# NTP_GPS_V1_0.net
KiCad netlist of a schematic drawn in EAGLE
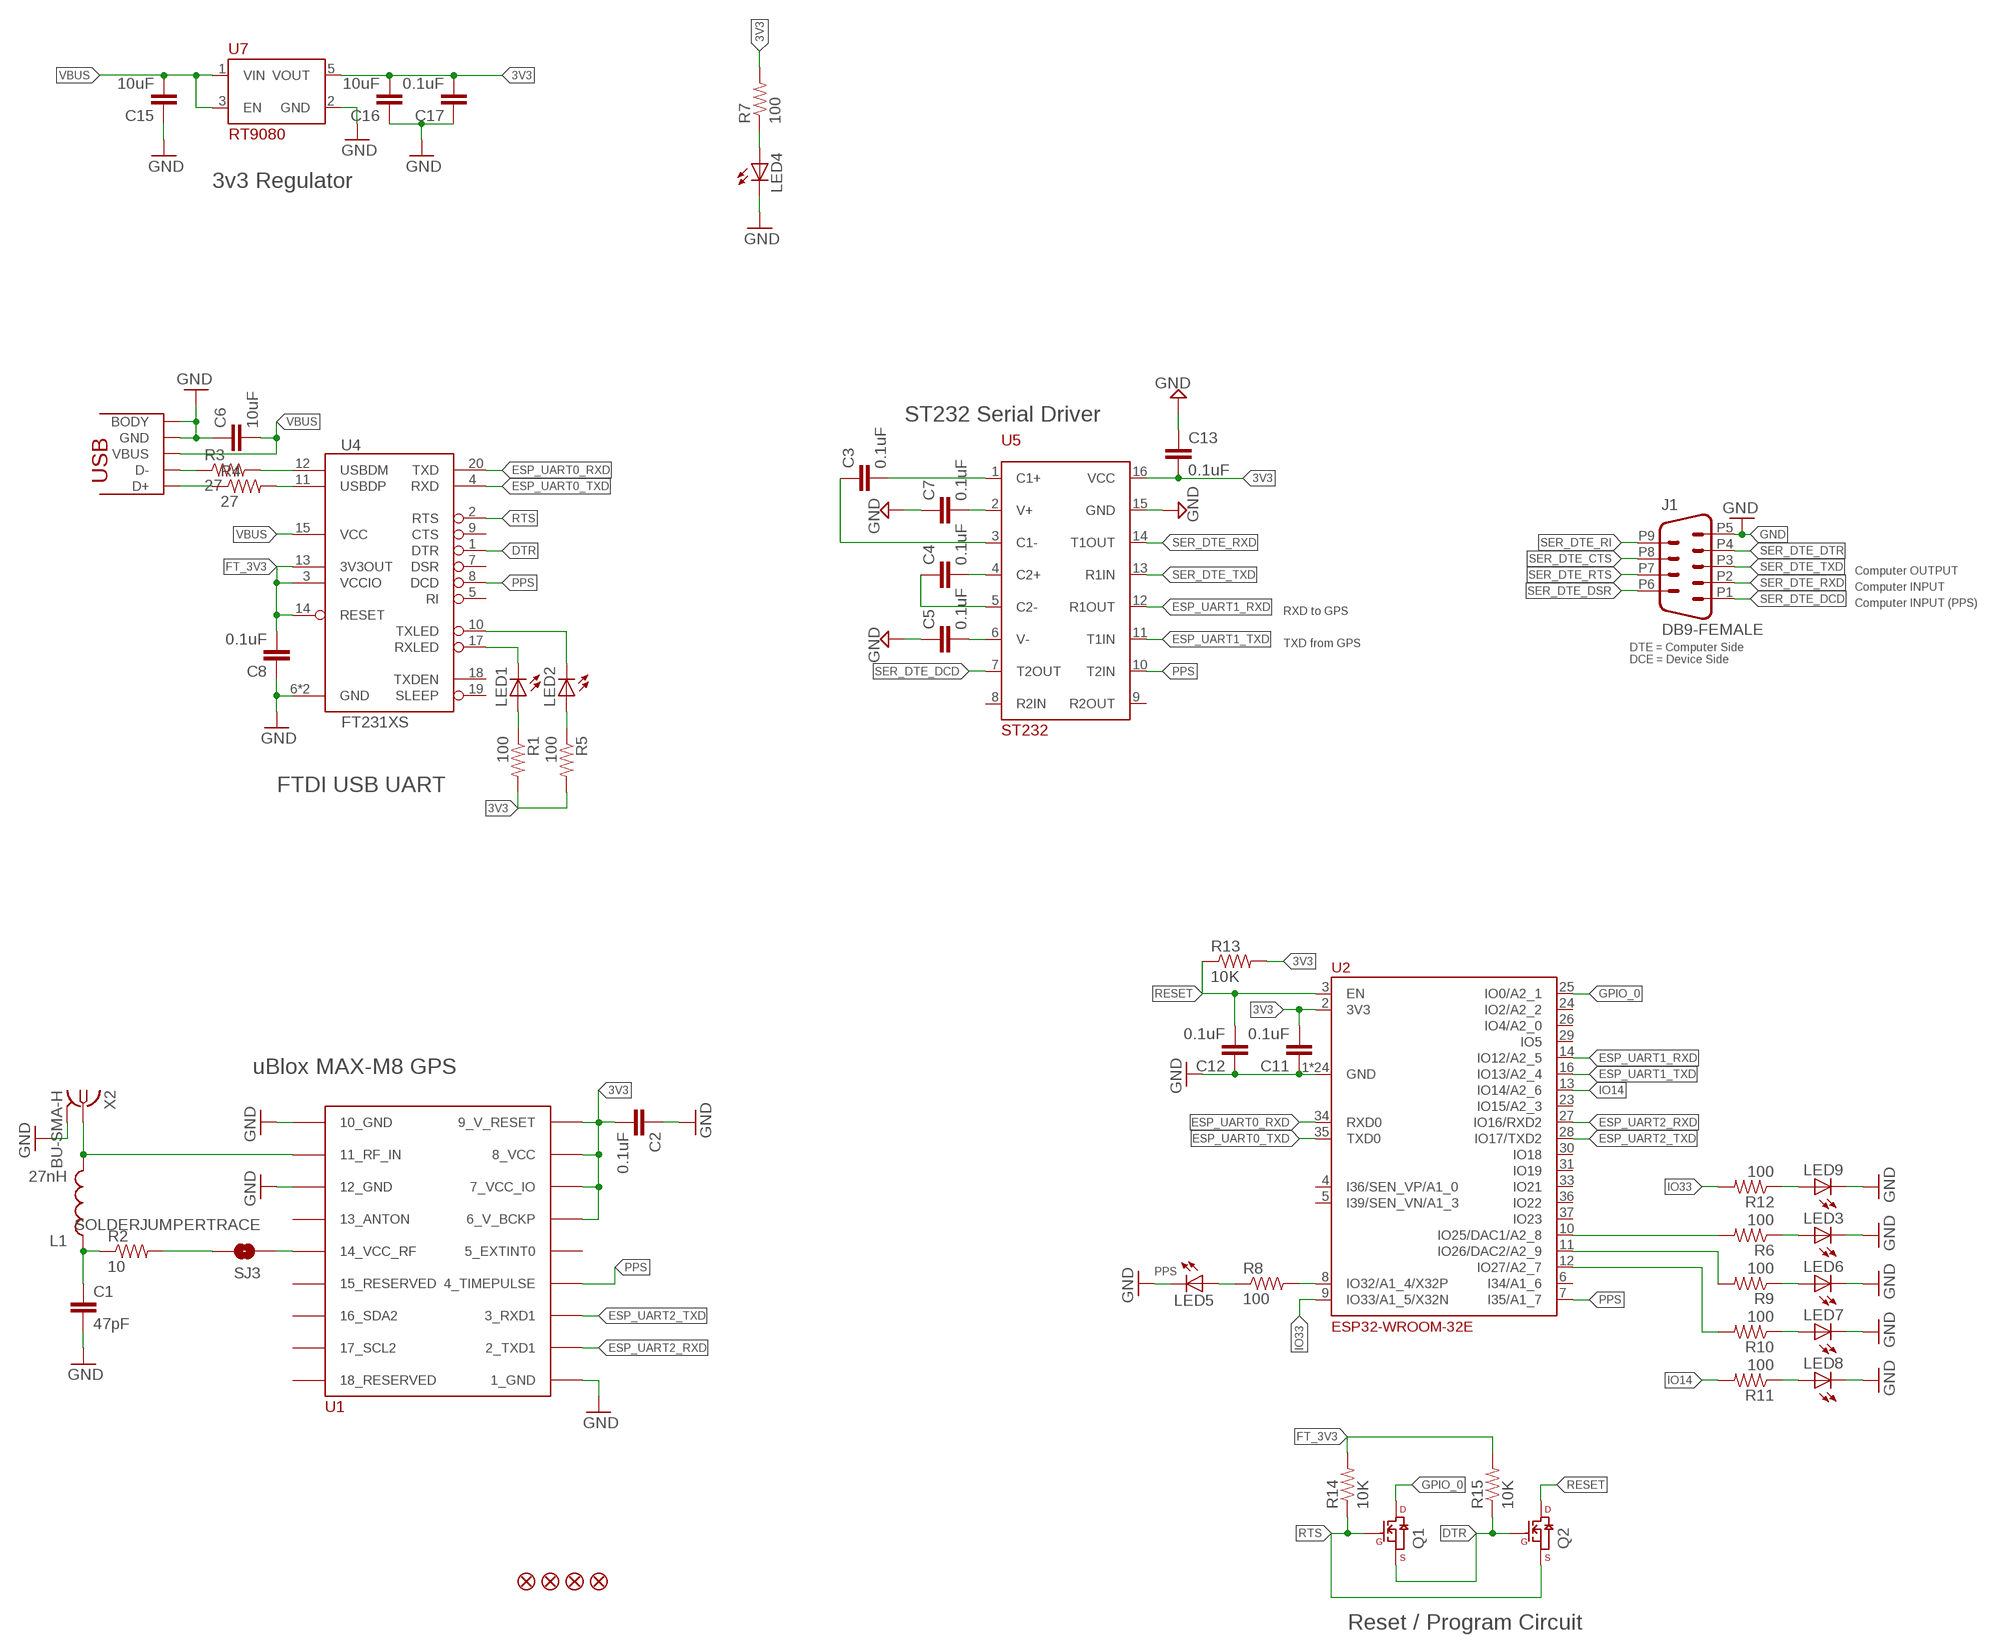
[diagram p0: schematic, sheet 1]

(export (version "E")
  (design (tool "Eeschema 10.0.6"))
  (components
    (comp (ref "C1")
      (value "47pF")
      (footprint "eagle-import:0603-CAP")
      (libsource (lib "eagle-import") (part "CAP0603-CAP"))
    )
    (comp (ref "C2")
      (value "0.1uF")
      (footprint "eagle-import:0603-CAP")
      (libsource (lib "eagle-import") (part "CAP0603-CAP"))
    )
    (comp (ref "C3")
      (value "0.1uF")
      (footprint "eagle-import:0603-CAP")
      (libsource (lib "eagle-import") (part "CAP0603-CAP"))
    )
    (comp (ref "C4")
      (value "0.1uF")
      (footprint "eagle-import:0603-CAP")
      (libsource (lib "eagle-import") (part "CAP0603-CAP"))
    )
    (comp (ref "C5")
      (value "0.1uF")
      (footprint "eagle-import:0603-CAP")
      (libsource (lib "eagle-import") (part "CAP0603-CAP"))
    )
    (comp (ref "C6")
      (value "10uF")
      (footprint "eagle-import:1206")
      (libsource (lib "eagle-import") (part "CAP1206"))
    )
    (comp (ref "C7")
      (value "0.1uF")
      (footprint "eagle-import:0603-CAP")
      (libsource (lib "eagle-import") (part "CAP0603-CAP"))
    )
    (comp (ref "C8")
      (value "0.1uF")
      (footprint "eagle-import:0603-CAP")
      (libsource (lib "eagle-import") (part "CAP0603-CAP"))
    )
    (comp (ref "C11")
      (value "0.1uF")
      (footprint "eagle-import:0603-CAP")
      (libsource (lib "eagle-import") (part "CAP0603-CAP"))
    )
    (comp (ref "C12")
      (value "0.1uF")
      (footprint "eagle-import:0603-CAP")
      (libsource (lib "eagle-import") (part "CAP0603-CAP"))
    )
    (comp (ref "C13")
      (value "0.1uF")
      (footprint "eagle-import:0603-CAP")
      (libsource (lib "eagle-import") (part "CAP0603-CAP"))
    )
    (comp (ref "C15")
      (value "10uF")
      (footprint "eagle-import:1206")
      (libsource (lib "eagle-import") (part "CAP1206"))
    )
    (comp (ref "C16")
      (value "10uF")
      (footprint "eagle-import:1206")
      (libsource (lib "eagle-import") (part "CAP1206"))
    )
    (comp (ref "C17")
      (value "0.1uF")
      (footprint "eagle-import:0603-CAP")
      (libsource (lib "eagle-import") (part "CAP0603-CAP"))
    )
    (comp (ref "FID1")
      (value "FIDUCIAL")
      (footprint "eagle-import:FIDUCIAL")
      (libsource (lib "eagle-import") (part "FIDUCIAL"))
    )
    (comp (ref "FID2")
      (value "FIDUCIAL")
      (footprint "eagle-import:FIDUCIAL")
      (libsource (lib "eagle-import") (part "FIDUCIAL"))
    )
    (comp (ref "FID3")
      (value "FIDUCIAL")
      (footprint "eagle-import:FIDUCIAL")
      (libsource (lib "eagle-import") (part "FIDUCIAL"))
    )
    (comp (ref "FID4")
      (value "FIDUCIAL")
      (footprint "eagle-import:FIDUCIAL")
      (libsource (lib "eagle-import") (part "FIDUCIAL"))
    )
    (comp (ref "J1")
      (value "DB9-FEMALE")
      (footprint "eagle-import:AMP_DELTAD_D09S13B4GV00LF")
      (libsource (lib "eagle-import") (part "DB9-FEMALE"))
    )
    (comp (ref "L1")
      (value "27nH")
      (footprint "eagle-import:0603")
      (libsource (lib "eagle-import") (part "INDUCTOR0603"))
    )
    (comp (ref "LED1")
      (value "LED")
      (footprint "eagle-import:LED_QBL7XX80D-MP4A")
      (libsource (lib "eagle-import") (part "LED"))
    )
    (comp (ref "LED2")
      (value "LED")
      (footprint "eagle-import:LED_QBL7XX80D-MP4A")
      (libsource (lib "eagle-import") (part "LED"))
    )
    (comp (ref "LED3")
      (value "LED")
      (footprint "eagle-import:LED_QBL7XX80D-MP4A")
      (libsource (lib "eagle-import") (part "LED"))
    )
    (comp (ref "LED4")
      (value "LED")
      (footprint "eagle-import:LED_QBL7XX80D-MP4A")
      (libsource (lib "eagle-import") (part "LED"))
    )
    (comp (ref "LED5")
      (value "LED")
      (footprint "eagle-import:LED_QBL7XX80D-MP4A")
      (libsource (lib "eagle-import") (part "LED"))
    )
    (comp (ref "LED6")
      (value "LED")
      (footprint "eagle-import:LED_QBL7XX80D-MP4A")
      (libsource (lib "eagle-import") (part "LED"))
    )
    (comp (ref "LED7")
      (value "LED")
      (footprint "eagle-import:LED_QBL7XX80D-MP4A")
      (libsource (lib "eagle-import") (part "LED"))
    )
    (comp (ref "LED8")
      (value "LED")
      (footprint "eagle-import:LED_QBL7XX80D-MP4A")
      (libsource (lib "eagle-import") (part "LED"))
    )
    (comp (ref "LED9")
      (value "LED")
      (footprint "eagle-import:LED_QBL7XX80D-MP4A")
      (libsource (lib "eagle-import") (part "LED"))
    )
    (comp (ref "Q1")
      (value "MOSFET_N_CHANNELSI1308")
      (footprint "eagle-import:SC-70-3")
      (libsource (lib "eagle-import") (part "MOSFET_N_CHANNELSI1308"))
    )
    (comp (ref "Q2")
      (value "MOSFET_N_CHANNELSI1308")
      (footprint "eagle-import:SC-70-3")
      (libsource (lib "eagle-import") (part "MOSFET_N_CHANNELSI1308"))
    )
    (comp (ref "R1")
      (value "100")
      (footprint "eagle-import:0603-RES")
      (libsource (lib "eagle-import") (part "RESISTOR0603-RES"))
    )
    (comp (ref "R2")
      (value "10")
      (footprint "eagle-import:0603-RES")
      (libsource (lib "eagle-import") (part "RESISTOR0603-RES"))
    )
    (comp (ref "R3")
      (value "27")
      (footprint "eagle-import:0603-RES")
      (libsource (lib "eagle-import") (part "RESISTOR0603-RES"))
    )
    (comp (ref "R4")
      (value "27")
      (footprint "eagle-import:0603-RES")
      (libsource (lib "eagle-import") (part "RESISTOR0603-RES"))
    )
    (comp (ref "R5")
      (value "100")
      (footprint "eagle-import:0603-RES")
      (libsource (lib "eagle-import") (part "RESISTOR0603-RES"))
    )
    (comp (ref "R6")
      (value "100")
      (footprint "eagle-import:0603-RES")
      (libsource (lib "eagle-import") (part "RESISTOR0603-RES"))
    )
    (comp (ref "R7")
      (value "100")
      (footprint "eagle-import:0603-RES")
      (libsource (lib "eagle-import") (part "RESISTOR0603-RES"))
    )
    (comp (ref "R8")
      (value "100")
      (footprint "eagle-import:0603-RES")
      (libsource (lib "eagle-import") (part "RESISTOR0603-RES"))
    )
    (comp (ref "R9")
      (value "100")
      (footprint "eagle-import:0603-RES")
      (libsource (lib "eagle-import") (part "RESISTOR0603-RES"))
    )
    (comp (ref "R10")
      (value "100")
      (footprint "eagle-import:0603-RES")
      (libsource (lib "eagle-import") (part "RESISTOR0603-RES"))
    )
    (comp (ref "R11")
      (value "100")
      (footprint "eagle-import:0603-RES")
      (libsource (lib "eagle-import") (part "RESISTOR0603-RES"))
    )
    (comp (ref "R12")
      (value "100")
      (footprint "eagle-import:0603-RES")
      (libsource (lib "eagle-import") (part "RESISTOR0603-RES"))
    )
    (comp (ref "R13")
      (value "10K")
      (footprint "eagle-import:0603-RES")
      (libsource (lib "eagle-import") (part "RESISTOR0603-RES"))
    )
    (comp (ref "R14")
      (value "10K")
      (footprint "eagle-import:0603-RES")
      (libsource (lib "eagle-import") (part "RESISTOR0603-RES"))
    )
    (comp (ref "R15")
      (value "10K")
      (footprint "eagle-import:0603-RES")
      (libsource (lib "eagle-import") (part "RESISTOR0603-RES"))
    )
    (comp (ref "SJ3")
      (value "SOLDERJUMPERTRACE")
      (footprint "eagle-import:SJ_2S-TRACE")
      (libsource (lib "eagle-import") (part "SOLDERJUMPERTRACE"))
    )
    (comp (ref "U$1")
      (value "USB-MICROB")
      (footprint "eagle-import:USB-MICROB-10118192")
      (libsource (lib "eagle-import") (part "USB-MICROB"))
    )
    (comp (ref "U1")
      (value "UBLOX_MAX")
      (footprint "eagle-import:UBLOX_MAX")
      (libsource (lib "eagle-import") (part "UBLOX_MAX"))
    )
    (comp (ref "U2")
      (value "ESP32-WROOM-32E")
      (footprint "eagle-import:ESP32-WROOM-32E")
      (libsource (lib "eagle-import") (part "ESP32-WROOM-32E"))
    )
    (comp (ref "U4")
      (value "FT231XS")
      (footprint "eagle-import:SSOP-20")
      (libsource (lib "eagle-import") (part "FT231XS"))
    )
    (comp (ref "U5")
      (value "ST232")
      (footprint "eagle-import:SSOP-16")
      (libsource (lib "eagle-import") (part "ST232"))
    )
    (comp (ref "U7")
      (value "RT9080")
      (footprint "eagle-import:SOT-23-5")
      (libsource (lib "eagle-import") (part "RT9080"))
    )
    (comp (ref "X2")
      (value "BU-SMA-H")
      (footprint "eagle-import:BU-SMA-H")
      (libsource (lib "eagle-import") (part "BU-SMA-H"))
    )
  )
  (nets
    (net (code "1") (name "3V3") (class "Default")
      (node (ref "C11") (pin "2") (pinfunction "2_2") (pintype "passive"))
      (node (ref "C13") (pin "2") (pinfunction "2_2") (pintype "passive"))
      (node (ref "C16") (pin "2") (pinfunction "2_2") (pintype "passive"))
      (node (ref "C17") (pin "2") (pinfunction "2_2") (pintype "passive"))
      (node (ref "C2") (pin "2") (pinfunction "2_2") (pintype "passive"))
      (node (ref "R1") (pin "2") (pinfunction "2_2") (pintype "passive"))
      (node (ref "R13") (pin "2") (pinfunction "2_2") (pintype "passive"))
      (node (ref "R5") (pin "2") (pinfunction "2_2") (pintype "passive"))
      (node (ref "R7") (pin "2") (pinfunction "2_2") (pintype "passive"))
      (node (ref "U1") (pin "6_V_BCKP") (pinfunction "6_V_BCKP_6_V_BCKP") (pintype "bidirectional"))
      (node (ref "U1") (pin "7_VCC_IO") (pinfunction "7_VCC_IO_7_VCC_IO") (pintype "power_in"))
      (node (ref "U1") (pin "8_VCC") (pinfunction "8_VCC_8_VCC") (pintype "power_in"))
      (node (ref "U1") (pin "9_V_RESET") (pinfunction "9_V_RESET_9_V_RESET") (pintype "power_in"))
      (node (ref "U2") (pin "2") (pinfunction "3V3_2") (pintype "power_in"))
      (node (ref "U5") (pin "16") (pinfunction "VCC_16") (pintype "bidirectional"))
      (node (ref "U7") (pin "5") (pinfunction "VOUT_5") (pintype "bidirectional"))
    )
    (net (code "2") (name "DTR") (class "Default")
      (node (ref "Q1") (pin "P$2") (pinfunction "S_P$2") (pintype "bidirectional"))
      (node (ref "Q2") (pin "P$1") (pinfunction "G_P$1") (pintype "bidirectional"))
      (node (ref "R15") (pin "1") (pinfunction "1_1") (pintype "passive"))
      (node (ref "U4") (pin "1") (pinfunction "DTR_1") (pintype "output"))
    )
    (net (code "3") (name "ESP_UART0_RXD") (class "Default")
      (node (ref "U2") (pin "34") (pinfunction "RXD0_34") (pintype "bidirectional"))
      (node (ref "U4") (pin "20") (pinfunction "TXD_20") (pintype "output"))
    )
    (net (code "4") (name "ESP_UART0_TXD") (class "Default")
      (node (ref "U2") (pin "35") (pinfunction "TXD0_35") (pintype "bidirectional"))
      (node (ref "U4") (pin "4") (pinfunction "RXD_4") (pintype "input"))
    )
    (net (code "5") (name "ESP_UART1_RXD") (class "Default")
      (node (ref "U2") (pin "14") (pinfunction "IO12/A2_5_14") (pintype "bidirectional"))
      (node (ref "U5") (pin "12") (pinfunction "R1OUT_12") (pintype "bidirectional"))
    )
    (net (code "6") (name "ESP_UART1_TXD") (class "Default")
      (node (ref "U2") (pin "16") (pinfunction "IO13/A2_4_16") (pintype "bidirectional"))
      (node (ref "U5") (pin "11") (pinfunction "T1IN_11") (pintype "bidirectional"))
    )
    (net (code "7") (name "ESP_UART2_RXD") (class "Default")
      (node (ref "U1") (pin "2_TXD1") (pinfunction "2_TXD1_2_TXD1") (pintype "bidirectional"))
      (node (ref "U2") (pin "27") (pinfunction "IO16/RXD2_27") (pintype "bidirectional"))
    )
    (net (code "8") (name "ESP_UART2_TXD") (class "Default")
      (node (ref "U1") (pin "3_RXD1") (pinfunction "3_RXD1_3_RXD1") (pintype "bidirectional"))
      (node (ref "U2") (pin "28") (pinfunction "IO17/TXD2_28") (pintype "bidirectional"))
    )
    (net (code "9") (name "FT_3V3") (class "Default")
      (node (ref "C8") (pin "2") (pinfunction "2_2") (pintype "passive"))
      (node (ref "R14") (pin "2") (pinfunction "2_2") (pintype "passive"))
      (node (ref "R15") (pin "2") (pinfunction "2_2") (pintype "passive"))
      (node (ref "U4") (pin "13") (pinfunction "3V3OUT_13") (pintype "output"))
      (node (ref "U4") (pin "14") (pinfunction "RESET_14") (pintype "input"))
      (node (ref "U4") (pin "3") (pinfunction "VCCIO_3") (pintype "power_in"))
    )
    (net (code "10") (name "GND") (class "Default")
      (node (ref "C1") (pin "2") (pinfunction "2_2") (pintype "passive"))
      (node (ref "C11") (pin "1") (pinfunction "1_1") (pintype "passive"))
      (node (ref "C12") (pin "1") (pinfunction "1_1") (pintype "passive"))
      (node (ref "C13") (pin "1") (pinfunction "1_1") (pintype "passive"))
      (node (ref "C15") (pin "1") (pinfunction "1_1") (pintype "passive"))
      (node (ref "C16") (pin "1") (pinfunction "1_1") (pintype "passive"))
      (node (ref "C17") (pin "1") (pinfunction "1_1") (pintype "passive"))
      (node (ref "C2") (pin "1") (pinfunction "1_1") (pintype "passive"))
      (node (ref "C5") (pin "1") (pinfunction "1_1") (pintype "passive"))
      (node (ref "C6") (pin "1") (pinfunction "1_1") (pintype "passive"))
      (node (ref "C7") (pin "1") (pinfunction "1_1") (pintype "passive"))
      (node (ref "C8") (pin "1") (pinfunction "1_1") (pintype "passive"))
      (node (ref "J1") (pin "P5") (pinfunction "5_P5") (pintype "passive"))
      (node (ref "LED3") (pin "C") (pinfunction "C_C") (pintype "passive"))
      (node (ref "LED4") (pin "C") (pinfunction "C_C") (pintype "passive"))
      (node (ref "LED5") (pin "C") (pinfunction "C_C") (pintype "passive"))
      (node (ref "LED6") (pin "C") (pinfunction "C_C") (pintype "passive"))
      (node (ref "LED7") (pin "C") (pinfunction "C_C") (pintype "passive"))
      (node (ref "LED8") (pin "C") (pinfunction "C_C") (pintype "passive"))
      (node (ref "LED9") (pin "C") (pinfunction "C_C") (pintype "passive"))
      (node (ref "U$1") (pin "5") (pinfunction "GND_5") (pintype "bidirectional"))
      (node (ref "U$1") (pin "BODY@1") (pinfunction "BODY_BODY@1") (pintype "bidirectional"))
      (node (ref "U$1") (pin "BODY@2") (pinfunction "BODY_BODY@2") (pintype "bidirectional"))
      (node (ref "U$1") (pin "BODY@3") (pinfunction "BODY_BODY@3") (pintype "bidirectional"))
      (node (ref "U$1") (pin "BODY@4") (pinfunction "BODY_BODY@4") (pintype "bidirectional"))
      (node (ref "U$1") (pin "BODY@5") (pinfunction "BODY_BODY@5") (pintype "bidirectional"))
      (node (ref "U$1") (pin "BODY@6") (pinfunction "BODY_BODY@6") (pintype "bidirectional"))
      (node (ref "U1") (pin "10_GND") (pinfunction "10_GND_10_GND") (pintype "power_in"))
      (node (ref "U1") (pin "12_GND") (pinfunction "12_GND_12_GND") (pintype "power_in"))
      (node (ref "U1") (pin "1_GND") (pinfunction "1_GND_1_GND") (pintype "power_in"))
      (node (ref "U2") (pin "1") (pinfunction "GND_1") (pintype "power_in"))
      (node (ref "U2") (pin "15") (pinfunction "GND_15") (pintype "power_in"))
      (node (ref "U2") (pin "38") (pinfunction "GND_38") (pintype "power_in"))
      (node (ref "U2") (pin "P$1") (pinfunction "GND_P$1") (pintype "power_in"))
      (node (ref "U2") (pin "P$10") (pinfunction "GND_P$10") (pintype "power_in"))
      (node (ref "U2") (pin "P$11") (pinfunction "GND_P$11") (pintype "power_in"))
      (node (ref "U2") (pin "P$12") (pinfunction "GND_P$12") (pintype "power_in"))
      (node (ref "U2") (pin "P$2") (pinfunction "GND_P$2") (pintype "power_in"))
      (node (ref "U2") (pin "P$3") (pinfunction "GND_P$3") (pintype "power_in"))
      (node (ref "U2") (pin "P$4") (pinfunction "GND_P$4") (pintype "power_in"))
      (node (ref "U2") (pin "P$5") (pinfunction "GND_P$5") (pintype "power_in"))
      (node (ref "U2") (pin "P$6") (pinfunction "GND_P$6") (pintype "power_in"))
      (node (ref "U2") (pin "P$7") (pinfunction "GND_P$7") (pintype "power_in"))
      (node (ref "U2") (pin "P$8") (pinfunction "GND_P$8") (pintype "power_in"))
      (node (ref "U2") (pin "P$9") (pinfunction "GND_P$9") (pintype "power_in"))
      (node (ref "U2") (pin "PAD@1") (pinfunction "GND_PAD@1") (pintype "power_in"))
      (node (ref "U2") (pin "PAD@2") (pinfunction "GND_PAD@2") (pintype "power_in"))
      (node (ref "U2") (pin "PAD@3") (pinfunction "GND_PAD@3") (pintype "power_in"))
      (node (ref "U2") (pin "PAD@4") (pinfunction "GND_PAD@4") (pintype "power_in"))
      (node (ref "U2") (pin "PAD@5") (pinfunction "GND_PAD@5") (pintype "power_in"))
      (node (ref "U2") (pin "PAD@6") (pinfunction "GND_PAD@6") (pintype "power_in"))
      (node (ref "U2") (pin "PAD@7") (pinfunction "GND_PAD@7") (pintype "power_in"))
      (node (ref "U2") (pin "PAD@8") (pinfunction "GND_PAD@8") (pintype "power_in"))
      (node (ref "U2") (pin "PAD@9") (pinfunction "GND_PAD@9") (pintype "power_in"))
      (node (ref "U4") (pin "16") (pinfunction "GND_16") (pintype "power_in"))
      (node (ref "U4") (pin "6") (pinfunction "GND_6") (pintype "power_in"))
      (node (ref "U5") (pin "15") (pinfunction "GND_15") (pintype "bidirectional"))
      (node (ref "U7") (pin "2") (pinfunction "GND_2") (pintype "bidirectional"))
      (node (ref "X2") (pin "2") (pinfunction "2_2") (pintype "passive"))
      (node (ref "X2") (pin "3") (pinfunction "2_3") (pintype "passive"))
      (node (ref "X2") (pin "4") (pinfunction "2_4") (pintype "passive"))
      (node (ref "X2") (pin "5") (pinfunction "2_5") (pintype "passive"))
    )
    (net (code "11") (name "GPIO_0") (class "Default")
      (node (ref "Q1") (pin "P$3") (pinfunction "D_P$3") (pintype "bidirectional"))
      (node (ref "U2") (pin "25") (pinfunction "IO0/A2_1_25") (pintype "bidirectional"))
    )
    (net (code "12") (name "IO14") (class "Default")
      (node (ref "R11") (pin "2") (pinfunction "2_2") (pintype "passive"))
      (node (ref "U2") (pin "13") (pinfunction "IO14/A2_6_13") (pintype "bidirectional"))
    )
    (net (code "13") (name "IO33") (class "Default")
      (node (ref "R12") (pin "2") (pinfunction "2_2") (pintype "passive"))
      (node (ref "U2") (pin "9") (pinfunction "IO33/A1_5/X32N_9") (pintype "bidirectional"))
    )
    (net (code "14") (name "Net-(C1-Pad1)") (class "Default")
      (node (ref "C1") (pin "1") (pinfunction "1_1") (pintype "passive"))
      (node (ref "L1") (pin "1") (pinfunction "1_1") (pintype "passive"))
      (node (ref "R2") (pin "1") (pinfunction "1_1") (pintype "passive"))
    )
    (net (code "15") (name "Net-(L1-Pad2)") (class "Default")
      (node (ref "L1") (pin "2") (pinfunction "2_2") (pintype "passive"))
      (node (ref "U1") (pin "11_RF_IN") (pinfunction "11_RF_IN_11_RF_IN") (pintype "bidirectional"))
      (node (ref "X2") (pin "1") (pinfunction "1_1") (pintype "passive"))
    )
    (net (code "16") (name "Net-(LED1-PadA)") (class "Default")
      (node (ref "LED1") (pin "A") (pinfunction "A_A") (pintype "passive"))
      (node (ref "R1") (pin "1") (pinfunction "1_1") (pintype "passive"))
    )
    (net (code "17") (name "Net-(LED2-PadA)") (class "Default")
      (node (ref "LED2") (pin "A") (pinfunction "A_A") (pintype "passive"))
      (node (ref "R5") (pin "1") (pinfunction "1_1") (pintype "passive"))
    )
    (net (code "18") (name "Net-(LED3-PadA)") (class "Default")
      (node (ref "LED3") (pin "A") (pinfunction "A_A") (pintype "passive"))
      (node (ref "R6") (pin "1") (pinfunction "1_1") (pintype "passive"))
    )
    (net (code "19") (name "Net-(LED4-PadA)") (class "Default")
      (node (ref "LED4") (pin "A") (pinfunction "A_A") (pintype "passive"))
      (node (ref "R7") (pin "1") (pinfunction "1_1") (pintype "passive"))
    )
    (net (code "20") (name "Net-(LED5-PadA)") (class "Default")
      (node (ref "LED5") (pin "A") (pinfunction "A_A") (pintype "passive"))
      (node (ref "R8") (pin "1") (pinfunction "1_1") (pintype "passive"))
    )
    (net (code "21") (name "Net-(LED6-PadA)") (class "Default")
      (node (ref "LED6") (pin "A") (pinfunction "A_A") (pintype "passive"))
      (node (ref "R9") (pin "1") (pinfunction "1_1") (pintype "passive"))
    )
    (net (code "22") (name "Net-(LED7-PadA)") (class "Default")
      (node (ref "LED7") (pin "A") (pinfunction "A_A") (pintype "passive"))
      (node (ref "R10") (pin "1") (pinfunction "1_1") (pintype "passive"))
    )
    (net (code "23") (name "Net-(LED8-PadA)") (class "Default")
      (node (ref "LED8") (pin "A") (pinfunction "A_A") (pintype "passive"))
      (node (ref "R11") (pin "1") (pinfunction "1_1") (pintype "passive"))
    )
    (net (code "24") (name "Net-(LED9-PadA)") (class "Default")
      (node (ref "LED9") (pin "A") (pinfunction "A_A") (pintype "passive"))
      (node (ref "R12") (pin "1") (pinfunction "1_1") (pintype "passive"))
    )
    (net (code "25") (name "Net-(R2-Pad2)") (class "Default")
      (node (ref "R2") (pin "2") (pinfunction "2_2") (pintype "passive"))
      (node (ref "SJ3") (pin "2") (pinfunction "2_2") (pintype "passive"))
    )
    (net (code "26") (name "Net-(SJ3-Pad1)") (class "Default")
      (node (ref "SJ3") (pin "1") (pinfunction "1_1") (pintype "passive"))
      (node (ref "U1") (pin "14_VCC_RF") (pinfunction "14_VCC_RF_14_VCC_RF") (pintype "bidirectional"))
    )
    (net (code "27") (name "Net-(U$1-D+)") (class "Default")
      (node (ref "R4") (pin "1") (pinfunction "1_1") (pintype "passive"))
      (node (ref "U$1") (pin "3") (pinfunction "D+_3") (pintype "bidirectional"))
    )
    (net (code "28") (name "Net-(U$1-D-)") (class "Default")
      (node (ref "R3") (pin "1") (pinfunction "1_1") (pintype "passive"))
      (node (ref "U$1") (pin "2") (pinfunction "D-_2") (pintype "bidirectional"))
    )
    (net (code "29") (name "Net-(U2-IO25{slash}DAC1{slash}A2_8)") (class "Default")
      (node (ref "R6") (pin "2") (pinfunction "2_2") (pintype "passive"))
      (node (ref "U2") (pin "10") (pinfunction "IO25/DAC1/A2_8_10") (pintype "bidirectional"))
    )
    (net (code "30") (name "Net-(U2-IO26{slash}DAC2{slash}A2_9)") (class "Default")
      (node (ref "R9") (pin "2") (pinfunction "2_2") (pintype "passive"))
      (node (ref "U2") (pin "11") (pinfunction "IO26/DAC2/A2_9_11") (pintype "bidirectional"))
    )
    (net (code "31") (name "Net-(U2-IO27{slash}A2_7)") (class "Default")
      (node (ref "R10") (pin "2") (pinfunction "2_2") (pintype "passive"))
      (node (ref "U2") (pin "12") (pinfunction "IO27/A2_7_12") (pintype "bidirectional"))
    )
    (net (code "32") (name "Net-(U2-IO32{slash}A1_4{slash}X32P)") (class "Default")
      (node (ref "R8") (pin "2") (pinfunction "2_2") (pintype "passive"))
      (node (ref "U2") (pin "8") (pinfunction "IO32/A1_4/X32P_8") (pintype "bidirectional"))
    )
    (net (code "33") (name "Net-(U4-RXLED)") (class "Default")
      (node (ref "LED1") (pin "C") (pinfunction "C_C") (pintype "passive"))
      (node (ref "U4") (pin "17") (pinfunction "RXLED_17") (pintype "input"))
    )
    (net (code "34") (name "Net-(U4-TXLED)") (class "Default")
      (node (ref "LED2") (pin "C") (pinfunction "C_C") (pintype "passive"))
      (node (ref "U4") (pin "10") (pinfunction "TXLED_10") (pintype "input"))
    )
    (net (code "35") (name "Net-(U4-USBDM)") (class "Default")
      (node (ref "R3") (pin "2") (pinfunction "2_2") (pintype "passive"))
      (node (ref "U4") (pin "12") (pinfunction "USBDM_12") (pintype "bidirectional"))
    )
    (net (code "36") (name "Net-(U4-USBDP)") (class "Default")
      (node (ref "R4") (pin "2") (pinfunction "2_2") (pintype "passive"))
      (node (ref "U4") (pin "11") (pinfunction "USBDP_11") (pintype "bidirectional"))
    )
    (net (code "37") (name "Net-(U5-C1+)") (class "Default")
      (node (ref "C3") (pin "2") (pinfunction "2_2") (pintype "passive"))
      (node (ref "U5") (pin "1") (pinfunction "C1+_1") (pintype "bidirectional"))
    )
    (net (code "38") (name "Net-(U5-C1-)") (class "Default")
      (node (ref "C3") (pin "1") (pinfunction "1_1") (pintype "passive"))
      (node (ref "U5") (pin "3") (pinfunction "C1-_3") (pintype "bidirectional"))
    )
    (net (code "39") (name "Net-(U5-C2+)") (class "Default")
      (node (ref "C4") (pin "2") (pinfunction "2_2") (pintype "passive"))
      (node (ref "U5") (pin "4") (pinfunction "C2+_4") (pintype "bidirectional"))
    )
    (net (code "40") (name "Net-(U5-C2-)") (class "Default")
      (node (ref "C4") (pin "1") (pinfunction "1_1") (pintype "passive"))
      (node (ref "U5") (pin "5") (pinfunction "C2-_5") (pintype "bidirectional"))
    )
    (net (code "41") (name "Net-(U5-V+)") (class "Default")
      (node (ref "C7") (pin "2") (pinfunction "2_2") (pintype "passive"))
      (node (ref "U5") (pin "2") (pinfunction "V+_2") (pintype "bidirectional"))
    )
    (net (code "42") (name "Net-(U5-V-)") (class "Default")
      (node (ref "C5") (pin "2") (pinfunction "2_2") (pintype "passive"))
      (node (ref "U5") (pin "6") (pinfunction "V-_6") (pintype "bidirectional"))
    )
    (net (code "43") (name "PPS") (class "Default")
      (node (ref "U1") (pin "4_TIMEPULSE") (pinfunction "4_TIMEPULSE_4_TIMEPULSE") (pintype "bidirectional"))
      (node (ref "U2") (pin "7") (pinfunction "I35/A1_7_7") (pintype "input"))
      (node (ref "U4") (pin "8") (pinfunction "DCD_8") (pintype "input"))
      (node (ref "U5") (pin "10") (pinfunction "T2IN_10") (pintype "bidirectional"))
    )
    (net (code "44") (name "RESET") (class "Default")
      (node (ref "C12") (pin "2") (pinfunction "2_2") (pintype "passive"))
      (node (ref "Q2") (pin "P$3") (pinfunction "D_P$3") (pintype "bidirectional"))
      (node (ref "R13") (pin "1") (pinfunction "1_1") (pintype "passive"))
      (node (ref "U2") (pin "3") (pinfunction "EN_3") (pintype "input"))
    )
    (net (code "45") (name "RTS") (class "Default")
      (node (ref "Q1") (pin "P$1") (pinfunction "G_P$1") (pintype "bidirectional"))
      (node (ref "Q2") (pin "P$2") (pinfunction "S_P$2") (pintype "bidirectional"))
      (node (ref "R14") (pin "1") (pinfunction "1_1") (pintype "passive"))
      (node (ref "U4") (pin "2") (pinfunction "RTS_2") (pintype "output"))
    )
    (net (code "46") (name "SER_DTE_CTS") (class "Default")
      (node (ref "J1") (pin "P8") (pinfunction "8_P8") (pintype "passive"))
    )
    (net (code "47") (name "SER_DTE_DCD") (class "Default")
      (node (ref "J1") (pin "P1") (pinfunction "1_P1") (pintype "passive"))
      (node (ref "U5") (pin "7") (pinfunction "T2OUT_7") (pintype "bidirectional"))
    )
    (net (code "48") (name "SER_DTE_DSR") (class "Default")
      (node (ref "J1") (pin "P6") (pinfunction "6_P6") (pintype "passive"))
    )
    (net (code "49") (name "SER_DTE_DTR") (class "Default")
      (node (ref "J1") (pin "P4") (pinfunction "4_P4") (pintype "passive"))
    )
    (net (code "50") (name "SER_DTE_RI") (class "Default")
      (node (ref "J1") (pin "P9") (pinfunction "9_P9") (pintype "passive"))
    )
    (net (code "51") (name "SER_DTE_RTS") (class "Default")
      (node (ref "J1") (pin "P7") (pinfunction "7_P7") (pintype "passive"))
    )
    (net (code "52") (name "SER_DTE_RXD") (class "Default")
      (node (ref "J1") (pin "P2") (pinfunction "2_P2") (pintype "passive"))
      (node (ref "U5") (pin "14") (pinfunction "T1OUT_14") (pintype "bidirectional"))
    )
    (net (code "53") (name "SER_DTE_TXD") (class "Default")
      (node (ref "J1") (pin "P3") (pinfunction "3_P3") (pintype "passive"))
      (node (ref "U5") (pin "13") (pinfunction "R1IN_13") (pintype "bidirectional"))
    )
    (net (code "54") (name "VBUS") (class "Default")
      (node (ref "C15") (pin "2") (pinfunction "2_2") (pintype "passive"))
      (node (ref "C6") (pin "2") (pinfunction "2_2") (pintype "passive"))
      (node (ref "U$1") (pin "1") (pinfunction "VBUS_1") (pintype "bidirectional"))
      (node (ref "U4") (pin "15") (pinfunction "VCC_15") (pintype "power_in"))
      (node (ref "U7") (pin "1") (pinfunction "VIN_1") (pintype "bidirectional"))
      (node (ref "U7") (pin "3") (pinfunction "EN_3") (pintype "bidirectional"))
    )
    (net (code "55") (name "unconnected-(U1-Pad5_EXTINT0)") (class "Default")
      (node (ref "U1") (pin "5_EXTINT0") (pinfunction "5_EXTINT0_5_EXTINT0") (pintype "bidirectional"))
    )
    (net (code "56") (name "unconnected-(U1-Pad13_ANTON)") (class "Default")
      (node (ref "U1") (pin "13_ANTON") (pinfunction "13_ANTON_13_ANTON") (pintype "bidirectional"))
    )
    (net (code "57") (name "unconnected-(U1-Pad15_RESERVED)") (class "Default")
      (node (ref "U1") (pin "15_RESERVED") (pinfunction "15_RESERVED_15_RESERVED") (pintype "bidirectional"))
    )
    (net (code "58") (name "unconnected-(U1-Pad16_SDA2)") (class "Default")
      (node (ref "U1") (pin "16_SDA2") (pinfunction "16_SDA2_16_SDA2") (pintype "bidirectional"))
    )
    (net (code "59") (name "unconnected-(U1-Pad17_SCL2)") (class "Default")
      (node (ref "U1") (pin "17_SCL2") (pinfunction "17_SCL2_17_SCL2") (pintype "bidirectional"))
    )
    (net (code "60") (name "unconnected-(U1-Pad18_RESERVED)") (class "Default")
      (node (ref "U1") (pin "18_RESERVED") (pinfunction "18_RESERVED_18_RESERVED") (pintype "bidirectional"))
    )
    (net (code "61") (name "unconnected-(U2-I34{slash}A1_6-Pad6)") (class "Default")
      (node (ref "U2") (pin "6") (pinfunction "I34/A1_6_6") (pintype "input"))
    )
    (net (code "62") (name "unconnected-(U2-I36{slash}SEN_VP{slash}A1_0-Pad4)") (class "Default")
      (node (ref "U2") (pin "4") (pinfunction "I36/SEN_VP/A1_0_4") (pintype "input"))
    )
    (net (code "63") (name "unconnected-(U2-I39{slash}SEN_VN{slash}A1_3-Pad5)") (class "Default")
      (node (ref "U2") (pin "5") (pinfunction "I39/SEN_VN/A1_3_5") (pintype "input"))
    )
    (net (code "64") (name "unconnected-(U2-IO2{slash}A2_2-Pad24)") (class "Default")
      (node (ref "U2") (pin "24") (pinfunction "IO2/A2_2_24") (pintype "bidirectional"))
    )
    (net (code "65") (name "unconnected-(U2-IO4{slash}A2_0-Pad26)") (class "Default")
      (node (ref "U2") (pin "26") (pinfunction "IO4/A2_0_26") (pintype "bidirectional"))
    )
    (net (code "66") (name "unconnected-(U2-IO5-Pad29)") (class "Default")
      (node (ref "U2") (pin "29") (pinfunction "IO5_29") (pintype "bidirectional"))
    )
    (net (code "67") (name "unconnected-(U2-IO15{slash}A2_3-Pad23)") (class "Default")
      (node (ref "U2") (pin "23") (pinfunction "IO15/A2_3_23") (pintype "bidirectional"))
    )
    (net (code "68") (name "unconnected-(U2-IO18-Pad30)") (class "Default")
      (node (ref "U2") (pin "30") (pinfunction "IO18_30") (pintype "bidirectional"))
    )
    (net (code "69") (name "unconnected-(U2-IO19-Pad31)") (class "Default")
      (node (ref "U2") (pin "31") (pinfunction "IO19_31") (pintype "bidirectional"))
    )
    (net (code "70") (name "unconnected-(U2-IO21-Pad33)") (class "Default")
      (node (ref "U2") (pin "33") (pinfunction "IO21_33") (pintype "bidirectional"))
    )
    (net (code "71") (name "unconnected-(U2-IO22-Pad36)") (class "Default")
      (node (ref "U2") (pin "36") (pinfunction "IO22_36") (pintype "bidirectional"))
    )
    (net (code "72") (name "unconnected-(U2-IO23-Pad37)") (class "Default")
      (node (ref "U2") (pin "37") (pinfunction "IO23_37") (pintype "bidirectional"))
    )
    (net (code "73") (name "unconnected-(U4-CTS-Pad9)") (class "Default")
      (node (ref "U4") (pin "9") (pinfunction "CTS_9") (pintype "input"))
    )
    (net (code "74") (name "unconnected-(U4-DSR-Pad7)") (class "Default")
      (node (ref "U4") (pin "7") (pinfunction "DSR_7") (pintype "input"))
    )
    (net (code "75") (name "unconnected-(U4-RI-Pad5)") (class "Default")
      (node (ref "U4") (pin "5") (pinfunction "RI_5") (pintype "input"))
    )
    (net (code "76") (name "unconnected-(U4-SLEEP-Pad19)") (class "Default")
      (node (ref "U4") (pin "19") (pinfunction "SLEEP_19") (pintype "input"))
    )
    (net (code "77") (name "unconnected-(U4-TXDEN-Pad18)") (class "Default")
      (node (ref "U4") (pin "18") (pinfunction "TXDEN_18") (pintype "input"))
    )
    (net (code "78") (name "unconnected-(U5-R2IN-Pad8)") (class "Default")
      (node (ref "U5") (pin "8") (pinfunction "R2IN_8") (pintype "bidirectional"))
    )
    (net (code "79") (name "unconnected-(U5-R2OUT-Pad9)") (class "Default")
      (node (ref "U5") (pin "9") (pinfunction "R2OUT_9") (pintype "bidirectional"))
    )
  )
)
